# Dust_Sensor_Bypass_adapter.net
KiCad netlist of a schematic drawn in EAGLE
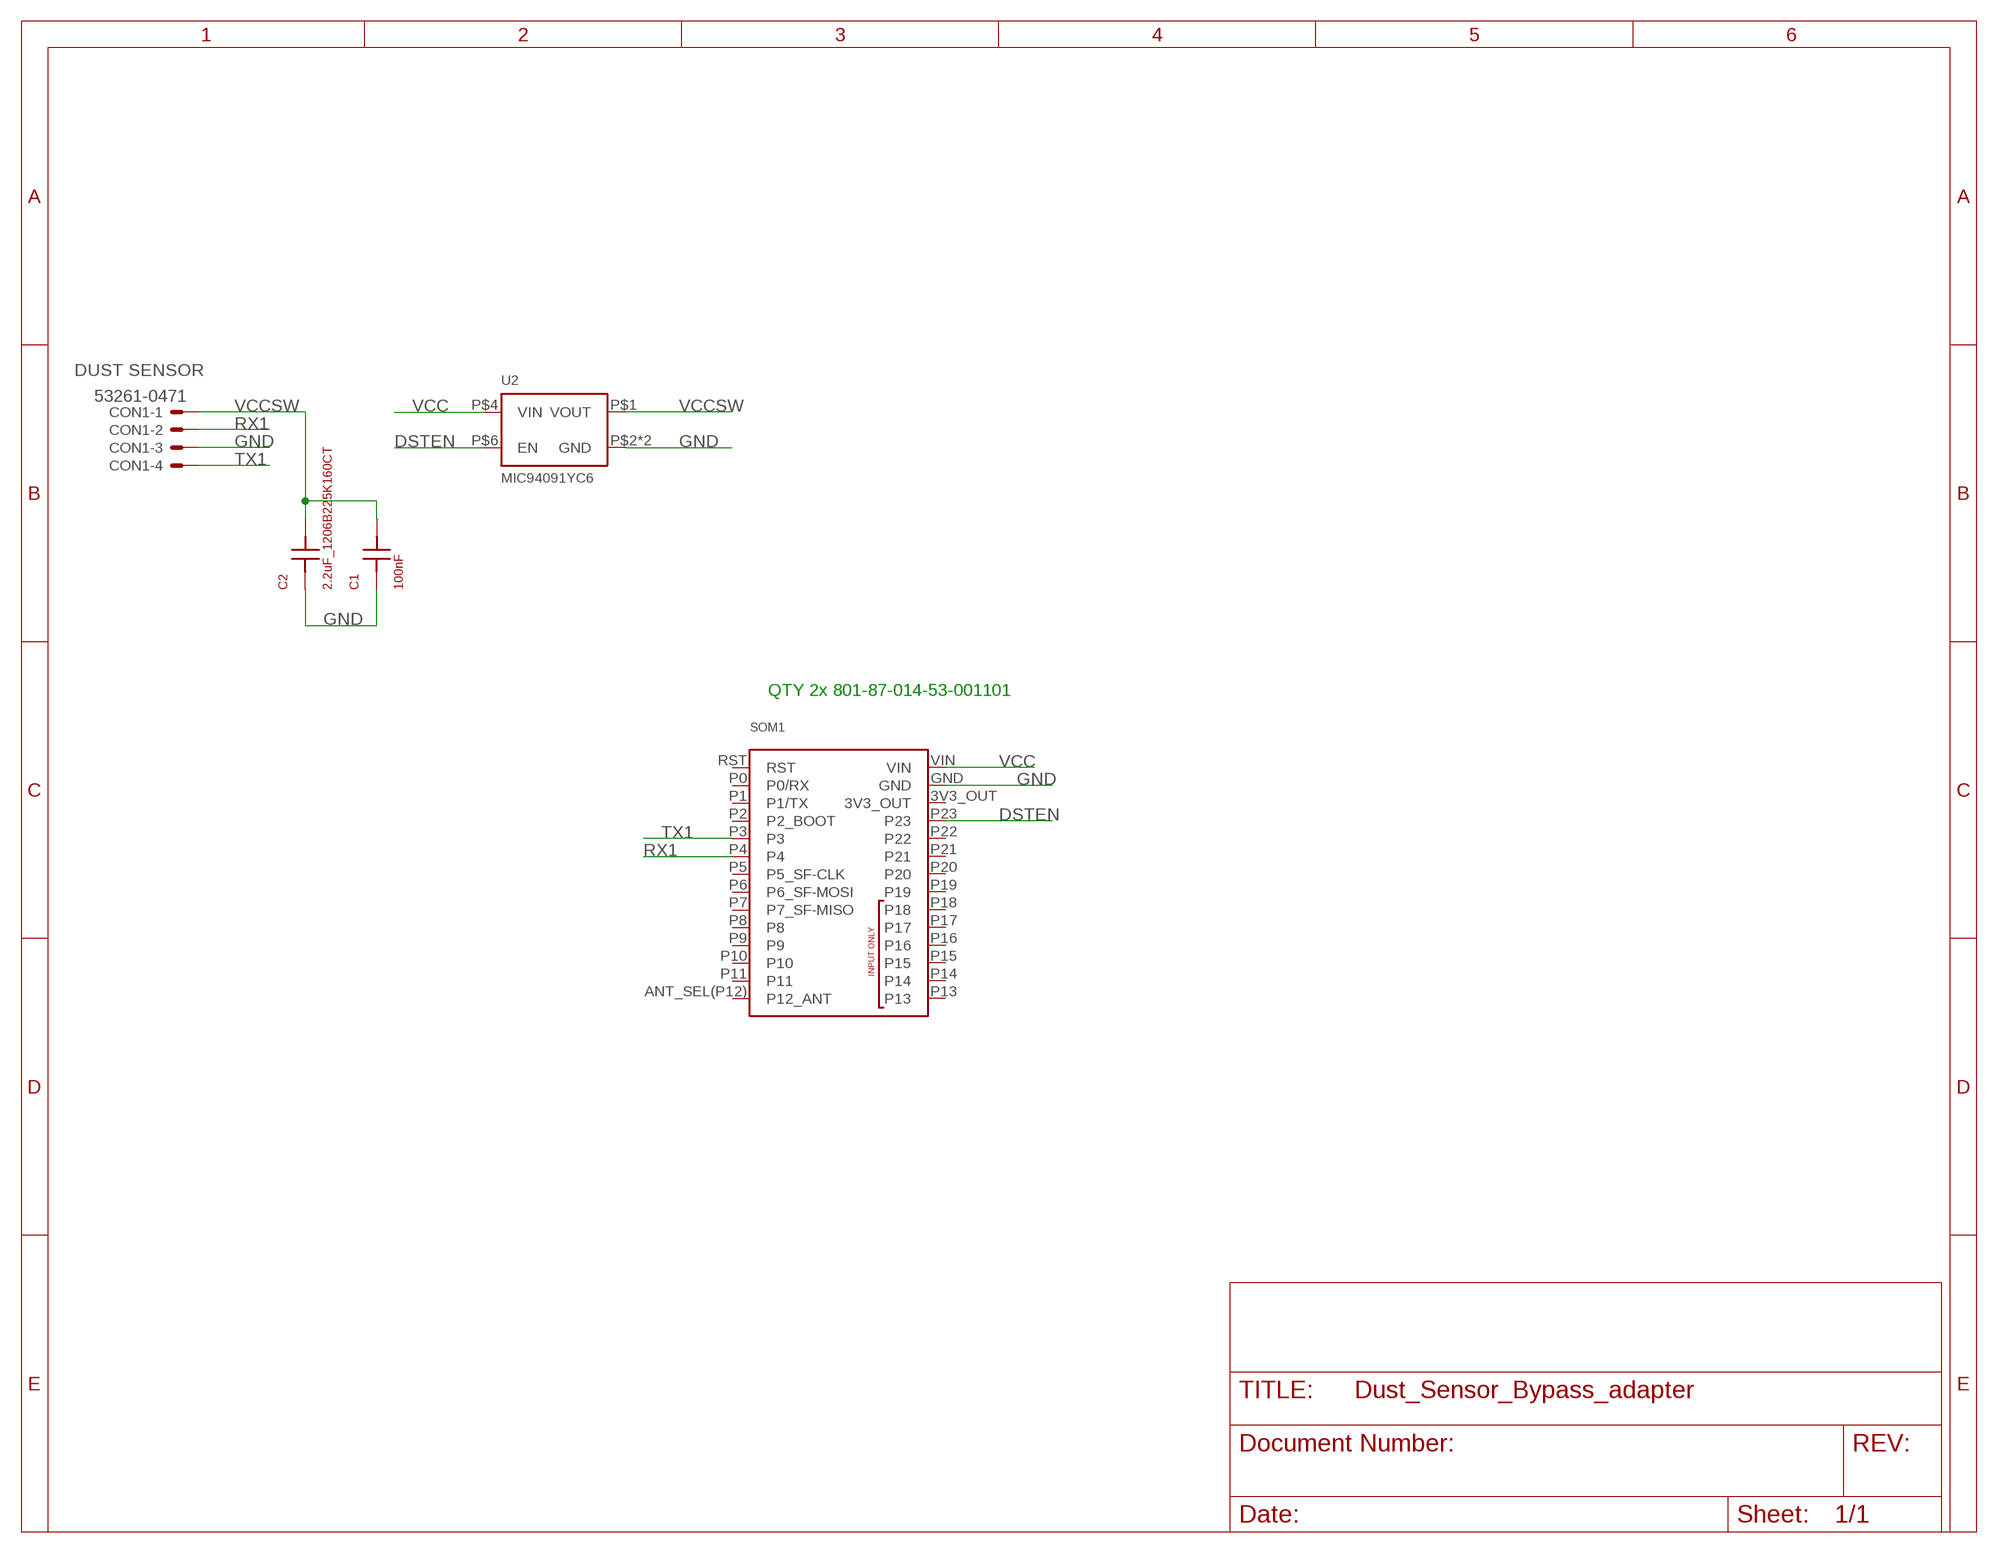
[diagram p0: schematic, sheet 1]

(export (version "E")
  (design (tool "Eeschema 10.0.6"))
  (components
    (comp (ref "C1")
      (value "100nF")
      (footprint "eagle-import:SMD_0603")
      (libsource (lib "eagle-import") (part "CAP_NP_0603"))
    )
    (comp (ref "C2")
      (value "2.2uF_1206B225K160CT")
      (footprint "eagle-import:SMD_1206")
      (libsource (lib "eagle-import") (part "CAP_NP_1206"))
    )
    (comp (ref "CON1")
      (value "53261-0471")
      (footprint "eagle-import:53261-04")
      (fields (field (name "MF") "MOLEX"))
      (libsource (lib "eagle-import") (part "53?-04261"))
    )
    (comp (ref "SOM1")
      (value "PYCOM_LOPY4PTH")
      (footprint "eagle-import:PYCOM_LOPY4_PTH")
      (libsource (lib "eagle-import") (part "PYCOM_LOPY4PTH"))
    )
    (comp (ref "U2")
      (value "MIC94091YC6")
      (footprint "eagle-import:SC-70(C6)")
      (libsource (lib "eagle-import") (part "MIC9409X-MICREL-HIGH-SIDE-LOAD-SW_SC70(C6)"))
    )
  )
  (nets
    (net (code "1") (name "/3V3_OUT") (class "Default")
      (node (ref "SOM1") (pin "3V3_OUT") (pinfunction "3V3_OUT_3V3_OUT") (pintype "power_in"))
    )
    (net (code "2") (name "/DSTEN") (class "Default")
      (node (ref "SOM1") (pin "P23") (pinfunction "P23_P23") (pintype "bidirectional"))
      (node (ref "U2") (pin "P$6") (pinfunction "EN_P$6") (pintype "input"))
    )
    (net (code "3") (name "/GND") (class "Default")
      (node (ref "C1") (pin "P$1") (pinfunction "P$1_P$1") (pintype "passive"))
      (node (ref "C2") (pin "P$1") (pinfunction "P$1_P$1") (pintype "passive"))
      (node (ref "CON1") (pin "3") (pinfunction "S_3") (pintype "passive"))
      (node (ref "SOM1") (pin "GND") (pinfunction "GND_GND") (pintype "power_in"))
      (node (ref "U2") (pin "P$2") (pinfunction "GND_P$2") (pintype "power_in"))
      (node (ref "U2") (pin "P$5") (pinfunction "GND_P$5") (pintype "power_in"))
    )
    (net (code "4") (name "/RX1") (class "Default")
      (node (ref "CON1") (pin "2") (pinfunction "S_2") (pintype "passive"))
      (node (ref "SOM1") (pin "P4") (pinfunction "P4_P4") (pintype "bidirectional"))
    )
    (net (code "5") (name "/TX1") (class "Default")
      (node (ref "CON1") (pin "4") (pinfunction "S_4") (pintype "passive"))
      (node (ref "SOM1") (pin "P3") (pinfunction "P3_P3") (pintype "bidirectional"))
    )
    (net (code "6") (name "/VCC") (class "Default")
      (node (ref "SOM1") (pin "VIN") (pinfunction "VIN_VIN") (pintype "power_in"))
      (node (ref "U2") (pin "P$4") (pinfunction "VIN_P$4") (pintype "power_in"))
    )
    (net (code "7") (name "/VCCSW") (class "Default")
      (node (ref "C1") (pin "P$2") (pinfunction "P$2_P$2") (pintype "passive"))
      (node (ref "C2") (pin "P$2") (pinfunction "P$2_P$2") (pintype "passive"))
      (node (ref "CON1") (pin "1") (pinfunction "S_1") (pintype "passive"))
      (node (ref "U2") (pin "P$1") (pinfunction "VOUT_P$1") (pintype "power_in"))
    )
    (net (code "8") (name "unconnected-(SOM1-P0{slash}RX-PadP0)") (class "Default")
      (node (ref "SOM1") (pin "P0") (pinfunction "P0/RX_P0") (pintype "bidirectional"))
    )
    (net (code "9") (name "unconnected-(SOM1-P1{slash}TX-PadP1)") (class "Default")
      (node (ref "SOM1") (pin "P1") (pinfunction "P1/TX_P1") (pintype "bidirectional"))
    )
    (net (code "10") (name "unconnected-(SOM1-P2_BOOT-PadP2)") (class "Default")
      (node (ref "SOM1") (pin "P2") (pinfunction "P2_BOOT_P2") (pintype "bidirectional"))
    )
    (net (code "11") (name "unconnected-(SOM1-P5_SF-CLK-PadP5)") (class "Default")
      (node (ref "SOM1") (pin "P5") (pinfunction "P5_SF-CLK_P5") (pintype "bidirectional"))
    )
    (net (code "12") (name "unconnected-(SOM1-P6_SF-MOSI-PadP6)") (class "Default")
      (node (ref "SOM1") (pin "P6") (pinfunction "P6_SF-MOSI_P6") (pintype "bidirectional"))
    )
    (net (code "13") (name "unconnected-(SOM1-P7_SF-MISO-PadP7)") (class "Default")
      (node (ref "SOM1") (pin "P7") (pinfunction "P7_SF-MISO_P7") (pintype "bidirectional"))
    )
    (net (code "14") (name "unconnected-(SOM1-P12_ANT-PadANT_SEL(P12))") (class "Default")
      (node (ref "SOM1") (pin "ANT_SEL(P12)") (pinfunction "P12_ANT_ANT_SEL(P12)") (pintype "bidirectional"))
    )
    (net (code "15") (name "unconnected-(SOM1-PadP8)") (class "Default")
      (node (ref "SOM1") (pin "P8") (pinfunction "P8_P8") (pintype "bidirectional"))
    )
    (net (code "16") (name "unconnected-(SOM1-PadP9)") (class "Default")
      (node (ref "SOM1") (pin "P9") (pinfunction "P9_P9") (pintype "bidirectional"))
    )
    (net (code "17") (name "unconnected-(SOM1-PadP10)") (class "Default")
      (node (ref "SOM1") (pin "P10") (pinfunction "P10_P10") (pintype "bidirectional"))
    )
    (net (code "18") (name "unconnected-(SOM1-PadP11)") (class "Default")
      (node (ref "SOM1") (pin "P11") (pinfunction "P11_P11") (pintype "bidirectional"))
    )
    (net (code "19") (name "unconnected-(SOM1-PadP13)") (class "Default")
      (node (ref "SOM1") (pin "P13") (pinfunction "P13_P13") (pintype "bidirectional"))
    )
    (net (code "20") (name "unconnected-(SOM1-PadP14)") (class "Default")
      (node (ref "SOM1") (pin "P14") (pinfunction "P14_P14") (pintype "bidirectional"))
    )
    (net (code "21") (name "unconnected-(SOM1-PadP15)") (class "Default")
      (node (ref "SOM1") (pin "P15") (pinfunction "P15_P15") (pintype "bidirectional"))
    )
    (net (code "22") (name "unconnected-(SOM1-PadP16)") (class "Default")
      (node (ref "SOM1") (pin "P16") (pinfunction "P16_P16") (pintype "bidirectional"))
    )
    (net (code "23") (name "unconnected-(SOM1-PadP17)") (class "Default")
      (node (ref "SOM1") (pin "P17") (pinfunction "P17_P17") (pintype "bidirectional"))
    )
    (net (code "24") (name "unconnected-(SOM1-PadP18)") (class "Default")
      (node (ref "SOM1") (pin "P18") (pinfunction "P18_P18") (pintype "bidirectional"))
    )
    (net (code "25") (name "unconnected-(SOM1-PadP19)") (class "Default")
      (node (ref "SOM1") (pin "P19") (pinfunction "P19_P19") (pintype "bidirectional"))
    )
    (net (code "26") (name "unconnected-(SOM1-PadP20)") (class "Default")
      (node (ref "SOM1") (pin "P20") (pinfunction "P20_P20") (pintype "bidirectional"))
    )
    (net (code "27") (name "unconnected-(SOM1-PadP21)") (class "Default")
      (node (ref "SOM1") (pin "P21") (pinfunction "P21_P21") (pintype "bidirectional"))
    )
    (net (code "28") (name "unconnected-(SOM1-PadP22)") (class "Default")
      (node (ref "SOM1") (pin "P22") (pinfunction "P22_P22") (pintype "bidirectional"))
    )
    (net (code "29") (name "unconnected-(SOM1-PadRST)") (class "Default")
      (node (ref "SOM1") (pin "RST") (pinfunction "RST_RST") (pintype "input"))
    )
  )
)
